# SOE-RF.net
KiCad netlist of a schematic drawn in Altium Designer
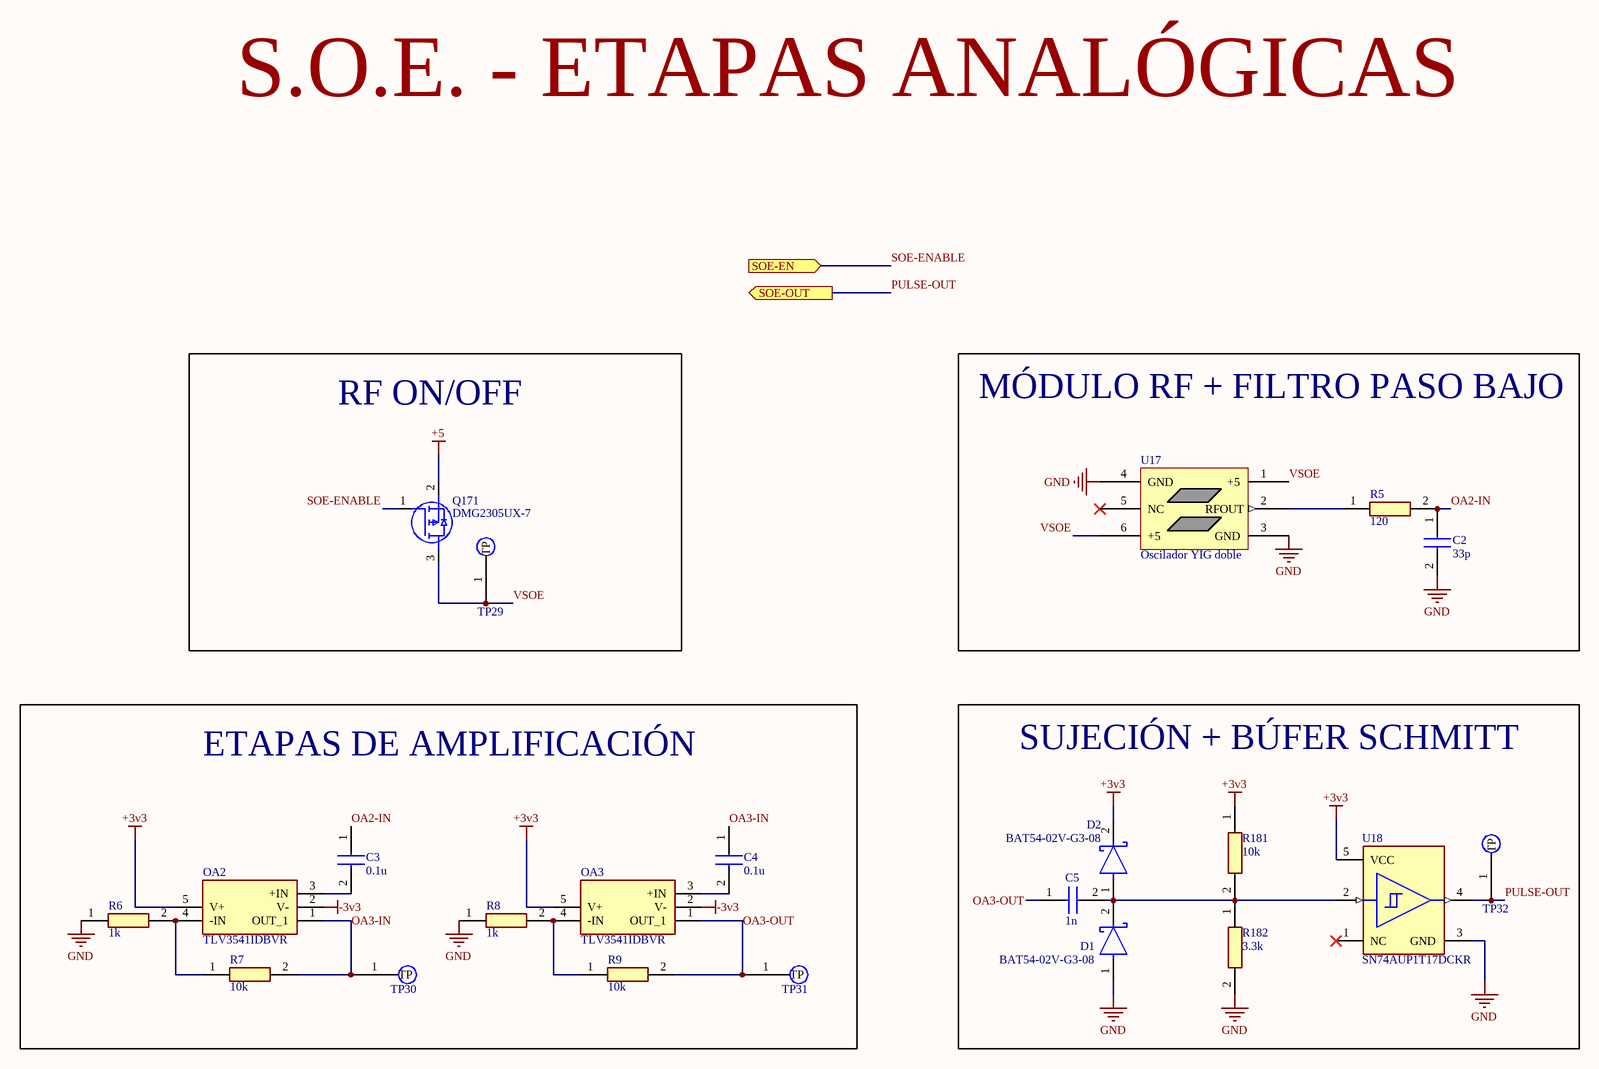
[diagram p0: SOE-RF.SchDoc]

(export (version "E")
  (design (tool "Eeschema 10.0.6"))
  (components
    (comp (ref "C2")
      (value "33p")
      (footprint "SamacSys:CAPC1608X90N")
      (description "Capacitor")
      (fields
        (field (name "MANUFACTURER_PART_NUMBER") "GRM1885C1H330GA01J")
        (field (name "MOUSER PART NUMBER") "81-GRM185C1H330GA01J")
      )
      (libsource (lib "*") (part "GRM1885C1H330GA01J"))
    )
    (comp (ref "C3")
      (value "0.1u")
      (footprint "SamacSys:CAPC1005X22N")
      (description "Capacitor")
      (fields
        (field (name "MANUFACTURER_PART_NUMBER") "GRM152R61A104KE19D")
        (field (name "MOUSER PART NUMBER") "81-GRM152R61A104KE9D")
      )
      (libsource (lib "*") (part "GRM152R61A104KE19D"))
    )
    (comp (ref "C4")
      (value "0.1u")
      (footprint "SamacSys:CAPC1005X22N")
      (description "Capacitor")
      (fields
        (field (name "MANUFACTURER_PART_NUMBER") "GRM152R61A104KE19D")
        (field (name "MOUSER PART NUMBER") "81-GRM152R61A104KE9D")
      )
      (libsource (lib "*") (part "GRM152R61A104KE19D"))
    )
    (comp (ref "C5")
      (value "1n")
      (footprint "SamacSys:CAPC1005X55N")
      (description "Capacitor")
      (fields
        (field (name "MANUFACTURER_PART_NUMBER") "C1005X7S2A102K050BB")
        (field (name "MOUSER PART NUMBER") "810-C1005X7S2A102K")
      )
      (libsource (lib "*") (part "C1005X7S2A102K050BB"))
    )
    (comp (ref "D1")
      (value "BAT54-02V-G3-08")
      (footprint "FP-S8-V-3880_02-003-MFG")
      (description "BAT54-02V-G3-08 Schottky Diode Sod52330V, 0.4V@10Ma, Ifmax=200Ma")
      (libsource (lib "Altium Content Vault") (part "360ad2f4ac25a952324d13796385471"))
    )
    (comp (ref "D2")
      (value "BAT54-02V-G3-08")
      (footprint "FP-S8-V-3880_02-003-MFG")
      (description "BAT54-02V-G3-08 Schottky Diode Sod52330V, 0.4V@10Ma, Ifmax=200Ma")
      (libsource (lib "Altium Content Vault") (part "360ad2f4ac25a952324d13796385471"))
    )
    (comp (ref "OA2")
      (value "TLV3541IDBVR")
      (footprint "SamacSys:SOT95P280X145-5N")
      (description "Integrated Circuit")
      (fields (field (name "MOUSER PART NUMBER") "595-TLV3541IDBVR"))
      (libsource (lib "*") (part "TLV3541IDBVR"))
    )
    (comp (ref "OA3")
      (value "TLV3541IDBVR")
      (footprint "SamacSys:SOT95P280X145-5N")
      (description "Integrated Circuit")
      (fields (field (name "MOUSER PART NUMBER") "595-TLV3541IDBVR"))
      (libsource (lib "*") (part "TLV3541IDBVR"))
    )
    (comp (ref "Q171")
      (value "DMG2305UX-7")
      (footprint "SamacSys:SOT96P240X115-3N")
      (description "MOSFET (P-Channel)")
      (fields (field (name "MOUSER PART NUMBER") "621-DMG2305UX-7"))
      (libsource (lib "*") (part "DMG2305UX-7"))
    )
    (comp (ref "R5")
      (value "120")
      (footprint "SamacSys:RESC1608X55N")
      (description "Resistor")
      (fields
        (field (name "MANUFACTURER_PART_NUMBER") "RC0603FR-07120RL")
        (field (name "MOUSER PART NUMBER") "603-RC0603FR-07120RL")
      )
      (libsource (lib "*") (part "RC0603FR-07120RL"))
    )
    (comp (ref "R6")
      (value "1k")
      (footprint "SamacSys:ERA6AEB101V")
      (description "Resistor")
      (fields
        (field (name "MANUFACTURER_PART_NUMBER") "ERA-6ARW102V")
        (field (name "MOUSER PART NUMBER") "667-ERA-6ARW102V")
      )
      (libsource (lib "*") (part "ERA-6ARW102V"))
    )
    (comp (ref "R7")
      (value "10k")
      (footprint "SamacSys:RESC1005X40N")
      (description "Resistor")
      (fields
        (field (name "MANUFACTURER_PART_NUMBER") "RCA040210K0JNED")
        (field (name "MOUSER PART NUMBER") "71-RCA040210K0JNED")
      )
      (libsource (lib "*") (part "RCA040210K0JNED"))
    )
    (comp (ref "R8")
      (value "1k")
      (footprint "SamacSys:ERA6AEB101V")
      (description "Resistor")
      (fields
        (field (name "MANUFACTURER_PART_NUMBER") "ERA-6ARW102V")
        (field (name "MOUSER PART NUMBER") "667-ERA-6ARW102V")
      )
      (libsource (lib "*") (part "ERA-6ARW102V"))
    )
    (comp (ref "R9")
      (value "10k")
      (footprint "SamacSys:RESC1005X40N")
      (description "Resistor")
      (fields
        (field (name "MANUFACTURER_PART_NUMBER") "RCA040210K0JNED")
        (field (name "MOUSER PART NUMBER") "71-RCA040210K0JNED")
      )
      (libsource (lib "*") (part "RCA040210K0JNED"))
    )
    (comp (ref "R181")
      (value "10k")
      (footprint "SamacSys:RESC1005X40N")
      (description "Resistor")
      (fields
        (field (name "MANUFACTURER_PART_NUMBER") "RCA040210K0JNED")
        (field (name "MOUSER PART NUMBER") "71-RCA040210K0JNED")
      )
      (libsource (lib "") (part "RCA040210K0JNED_1"))
    )
    (comp (ref "R182")
      (value "3.3k")
      (footprint "SamacSys:ERA3AEB101V")
      (description "Resistor")
      (fields
        (field (name "MANUFACTURER_PART_NUMBER") "ERA-3ARB332V")
        (field (name "MOUSER PART NUMBER") "667-ERA-3ARB332V")
      )
      (libsource (lib "*") (part "ERA-3ARB332V"))
    )
    (comp (ref "TP29")
      (value "Testpoint")
      (footprint "Testpoint_TH")
      (libsource (lib "headers") (part "Testpoint"))
    )
    (comp (ref "TP30")
      (value "Testpoint")
      (footprint "TESTPOINT_SMD")
      (libsource (lib "headers") (part "Testpoint"))
    )
    (comp (ref "TP31")
      (value "Testpoint")
      (footprint "TESTPOINT_SMD")
      (libsource (lib "headers") (part "Testpoint"))
    )
    (comp (ref "TP32")
      (value "Testpoint")
      (footprint "TESTPOINT_SMD")
      (libsource (lib "headers") (part "Testpoint"))
    )
    (comp (ref "U17")
      (value "Oscilador YIG doble")
      (footprint "RF-MODULE-DOUBLE-COMPAT")
      (libsource (lib "SWS-CROSS") (part "SWS_MODULE_CROSS"))
    )
    (comp (ref "U18")
      (value "SN74AUP1T17DCKR")
      (footprint "FP-DCK0005A-IPC_B")
      (description "IC BUF NON-INVERT 3.6V SC70-5")
      (libsource (lib "Altium Content Vault") (part "13663c114c60c392ae5ab8dc83cb180"))
    )
  )
  (nets
    (net (code "1") (name "+3v3") (class "Default")
      (node (ref "D2") (pin "2") (pinfunction "C_2") (pintype "passive"))
      (node (ref "OA2") (pin "5") (pinfunction "V+_5") (pintype "passive"))
      (node (ref "OA3") (pin "5") (pinfunction "V+_5") (pintype "passive"))
      (node (ref "R181") (pin "1") (pinfunction "1_1") (pintype "passive"))
      (node (ref "U18") (pin "5") (pinfunction "VCC_5") (pintype "power_in"))
    )
    (net (code "2") (name "+5") (class "Default")
      (node (ref "Q171") (pin "2") (pinfunction "S_2") (pintype "passive"))
    )
    (net (code "3") (name "-3v3") (class "Default")
      (node (ref "OA2") (pin "2") (pinfunction "V-_2") (pintype "passive"))
      (node (ref "OA3") (pin "2") (pinfunction "V-_2") (pintype "passive"))
    )
    (net (code "4") (name "/OA2-IN") (class "Default")
      (node (ref "C2") (pin "1") (pinfunction "1_1") (pintype "passive"))
      (node (ref "C3") (pin "1") (pinfunction "1_1") (pintype "passive"))
      (node (ref "R5") (pin "2") (pinfunction "2_2") (pintype "passive"))
    )
    (net (code "5") (name "/OA3-IN") (class "Default")
      (node (ref "C4") (pin "1") (pinfunction "1_1") (pintype "passive"))
      (node (ref "OA2") (pin "1") (pinfunction "OUT_1_1") (pintype "passive"))
      (node (ref "R7") (pin "2") (pinfunction "2_2") (pintype "passive"))
      (node (ref "TP30") (pin "1") (pinfunction "TP_1") (pintype "passive"))
    )
    (net (code "6") (name "/OA3-OUT") (class "Default")
      (node (ref "C5") (pin "1") (pinfunction "1_1") (pintype "passive"))
      (node (ref "OA3") (pin "1") (pinfunction "OUT_1_1") (pintype "passive"))
      (node (ref "R9") (pin "2") (pinfunction "2_2") (pintype "passive"))
      (node (ref "TP31") (pin "1") (pinfunction "TP_1") (pintype "passive"))
    )
    (net (code "7") (name "/PULSE-OUT") (class "Default")
      (node (ref "TP32") (pin "1") (pinfunction "TP_1") (pintype "passive"))
      (node (ref "U18") (pin "4") (pinfunction "Y_4") (pintype "output"))
    )
    (net (code "8") (name "/SOE-ENABLE") (class "Default")
      (node (ref "Q171") (pin "1") (pinfunction "G_1") (pintype "passive"))
    )
    (net (code "9") (name "/VSOE") (class "Default")
      (node (ref "Q171") (pin "3") (pinfunction "D_3") (pintype "passive"))
      (node (ref "TP29") (pin "1") (pinfunction "TP_1") (pintype "passive"))
      (node (ref "U17") (pin "1") (pinfunction "+5_1") (pintype "power_in"))
      (node (ref "U17") (pin "6") (pinfunction "+5_6") (pintype "power_in"))
    )
    (net (code "10") (name "GND") (class "Default")
      (node (ref "C2") (pin "2") (pinfunction "2_2") (pintype "passive"))
      (node (ref "D1") (pin "1") (pinfunction "A_1") (pintype "passive"))
      (node (ref "R182") (pin "2") (pinfunction "2_2") (pintype "passive"))
      (node (ref "R6") (pin "1") (pinfunction "1_1") (pintype "passive"))
      (node (ref "R8") (pin "1") (pinfunction "1_1") (pintype "passive"))
      (node (ref "U17") (pin "3") (pinfunction "GND_3") (pintype "power_in"))
      (node (ref "U17") (pin "4") (pinfunction "GND_4") (pintype "power_in"))
      (node (ref "U18") (pin "3") (pinfunction "GND_3") (pintype "power_in"))
    )
    (net (code "11") (name "Net-(D1-C)") (class "Default")
      (node (ref "C5") (pin "2") (pinfunction "2_2") (pintype "passive"))
      (node (ref "D1") (pin "2") (pinfunction "C_2") (pintype "passive"))
      (node (ref "D2") (pin "1") (pinfunction "A_1") (pintype "passive"))
      (node (ref "R181") (pin "2") (pinfunction "2_2") (pintype "passive"))
      (node (ref "R182") (pin "1") (pinfunction "1_1") (pintype "passive"))
      (node (ref "U18") (pin "2") (pinfunction "A_2") (pintype "input"))
    )
    (net (code "12") (name "Net-(OA2-+IN)") (class "Default")
      (node (ref "C3") (pin "2") (pinfunction "2_2") (pintype "passive"))
      (node (ref "OA2") (pin "3") (pinfunction "+IN_3") (pintype "passive"))
    )
    (net (code "13") (name "Net-(OA2--IN)") (class "Default")
      (node (ref "OA2") (pin "4") (pinfunction "-IN_4") (pintype "passive"))
      (node (ref "R6") (pin "2") (pinfunction "2_2") (pintype "passive"))
      (node (ref "R7") (pin "1") (pinfunction "1_1") (pintype "passive"))
    )
    (net (code "14") (name "Net-(OA3-+IN)") (class "Default")
      (node (ref "C4") (pin "2") (pinfunction "2_2") (pintype "passive"))
      (node (ref "OA3") (pin "3") (pinfunction "+IN_3") (pintype "passive"))
    )
    (net (code "15") (name "Net-(OA3--IN)") (class "Default")
      (node (ref "OA3") (pin "4") (pinfunction "-IN_4") (pintype "passive"))
      (node (ref "R8") (pin "2") (pinfunction "2_2") (pintype "passive"))
      (node (ref "R9") (pin "1") (pinfunction "1_1") (pintype "passive"))
    )
    (net (code "16") (name "Net-(U17-RFOUT)") (class "Default")
      (node (ref "R5") (pin "1") (pinfunction "1_1") (pintype "passive"))
      (node (ref "U17") (pin "2") (pinfunction "RFOUT_2") (pintype "output"))
    )
    (net (code "17") (name "unconnected-(U17-NC-Pad5)") (class "Default")
      (node (ref "U17") (pin "5") (pinfunction "NC_5") (pintype "passive+no_connect"))
    )
    (net (code "18") (name "unconnected-(U18-NC-Pad1)") (class "Default")
      (node (ref "U18") (pin "1") (pinfunction "NC_1") (pintype "passive+no_connect"))
    )
  )
)
